# FuelPump.net
KiCad netlist of a schematic drawn in Altium Designer
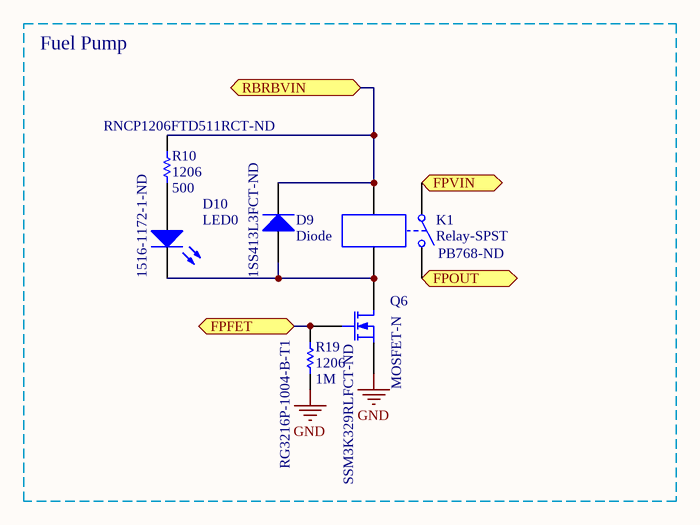
[diagram p0: FuelPump.SchDoc]

(export (version "E")
  (design (tool "Eeschema 10.0.6"))
  (components
    (comp (ref "D9")
      (value "Diode")
      (footprint "1SS413")
      (description "Switching diode")
      (fields
        (field (name "SUPPLIER PART NUMBER 1") "1SS413L3FCT-ND")
        (field (name "PUBLISHER") "Altium Limited")
      )
      (libsource (lib "Miscellaneous Devices") (part "Diode"))
    )
    (comp (ref "D10")
      (value "LED0")
      (footprint "C1206")
      (description "Typical INFRARED GaAs LED")
      (fields
        (field (name "SUPPLIER PART NUMBER 1") "1516-1172-1-ND")
        (field (name "PUBLISHER") "Altium Limited")
      )
      (libsource (lib "Miscellaneous Devices") (part "LED0"))
    )
    (comp (ref "K1")
      (value "Relay-SPST")
      (footprint "PB114012")
      (description "Single-Pole Single-Throw Relay")
      (fields (field (name "SUPPLIER PART NUMBER 1") "PB768-ND") (field (name "PUBLISHER") "Altium Limited"))
      (libsource (lib "Miscellaneous Devices") (part "Relay-SPST"))
    )
    (comp (ref "Q6")
      (value "MOSFET-N")
      (footprint "SOT23f")
      (description "N-Channel MOSFET")
      (fields
        (field (name "SUPPLIER PART NUMBER 1") "SSM3K329RLFCT-ND")
        (field (name "PUBLISHER") "Altium Limited")
      )
      (libsource (lib "Miscellaneous Devices") (part "MOSFET-N"))
    )
    (comp (ref "R10")
      (value "1206")
      (footprint "C1206")
      (description "Resistor")
      (fields
        (field (name "ALTIUM_VALUE") "500")
        (field (name "SUPPLIER PART NUMBER 1") "RNCP1206FTD511RCT-ND")
        (field (name "PUBLISHER") "Altium Limited")
      )
      (libsource (lib "Miscellaneous Devices") (part "Res1"))
    )
    (comp (ref "R19")
      (value "1206")
      (footprint "1206 (High Density)")
      (description "Resistor")
      (fields
        (field (name "ALTIUM_VALUE") "1M")
        (field (name "SUPPLIER PART NUMBER 1") "RG3216P-1004-B-T1")
        (field (name "PUBLISHER") "Altium Limited")
      )
      (libsource (lib "Miscellaneous Devices") (part "Res1"))
    )
  )
  (nets
    (net (code "1") (name "/FPFET") (class "Default")
      (node (ref "Q6") (pin "2") (pinfunction "G_2") (pintype "passive"))
      (node (ref "R19") (pin "2") (pinfunction "2_2") (pintype "passive"))
    )
    (net (code "2") (name "/FPOUT") (class "Default")
      (node (ref "K1") (pin "2") (pinfunction "2_2") (pintype "passive"))
    )
    (net (code "3") (name "/FPVIN") (class "Default")
      (node (ref "K1") (pin "1") (pinfunction "1_1") (pintype "passive"))
    )
    (net (code "4") (name "/RBRBVIN") (class "Default")
      (node (ref "D9") (pin "2") (pinfunction "K_2") (pintype "passive"))
      (node (ref "K1") (pin "3") (pinfunction "3_3") (pintype "passive"))
      (node (ref "R10") (pin "1") (pinfunction "1_1") (pintype "passive"))
    )
    (net (code "5") (name "GND") (class "Default")
      (node (ref "Q6") (pin "3") (pinfunction "S_3") (pintype "passive"))
      (node (ref "R19") (pin "1") (pinfunction "1_1") (pintype "passive"))
    )
    (net (code "6") (name "Net-(D10-A)") (class "Default")
      (node (ref "D10") (pin "1") (pinfunction "A_1") (pintype "passive"))
      (node (ref "R10") (pin "2") (pinfunction "2_2") (pintype "passive"))
    )
    (net (code "7") (name "Net-(D10-K)") (class "Default")
      (node (ref "D10") (pin "2") (pinfunction "K_2") (pintype "passive"))
      (node (ref "D9") (pin "1") (pinfunction "A_1") (pintype "passive"))
      (node (ref "K1") (pin "4") (pinfunction "4_4") (pintype "passive"))
      (node (ref "Q6") (pin "1") (pinfunction "D_1") (pintype "passive"))
    )
  )
)
